# Switch_Video_con_PIC.net
KiCad netlist of a schematic drawn in Altium Designer
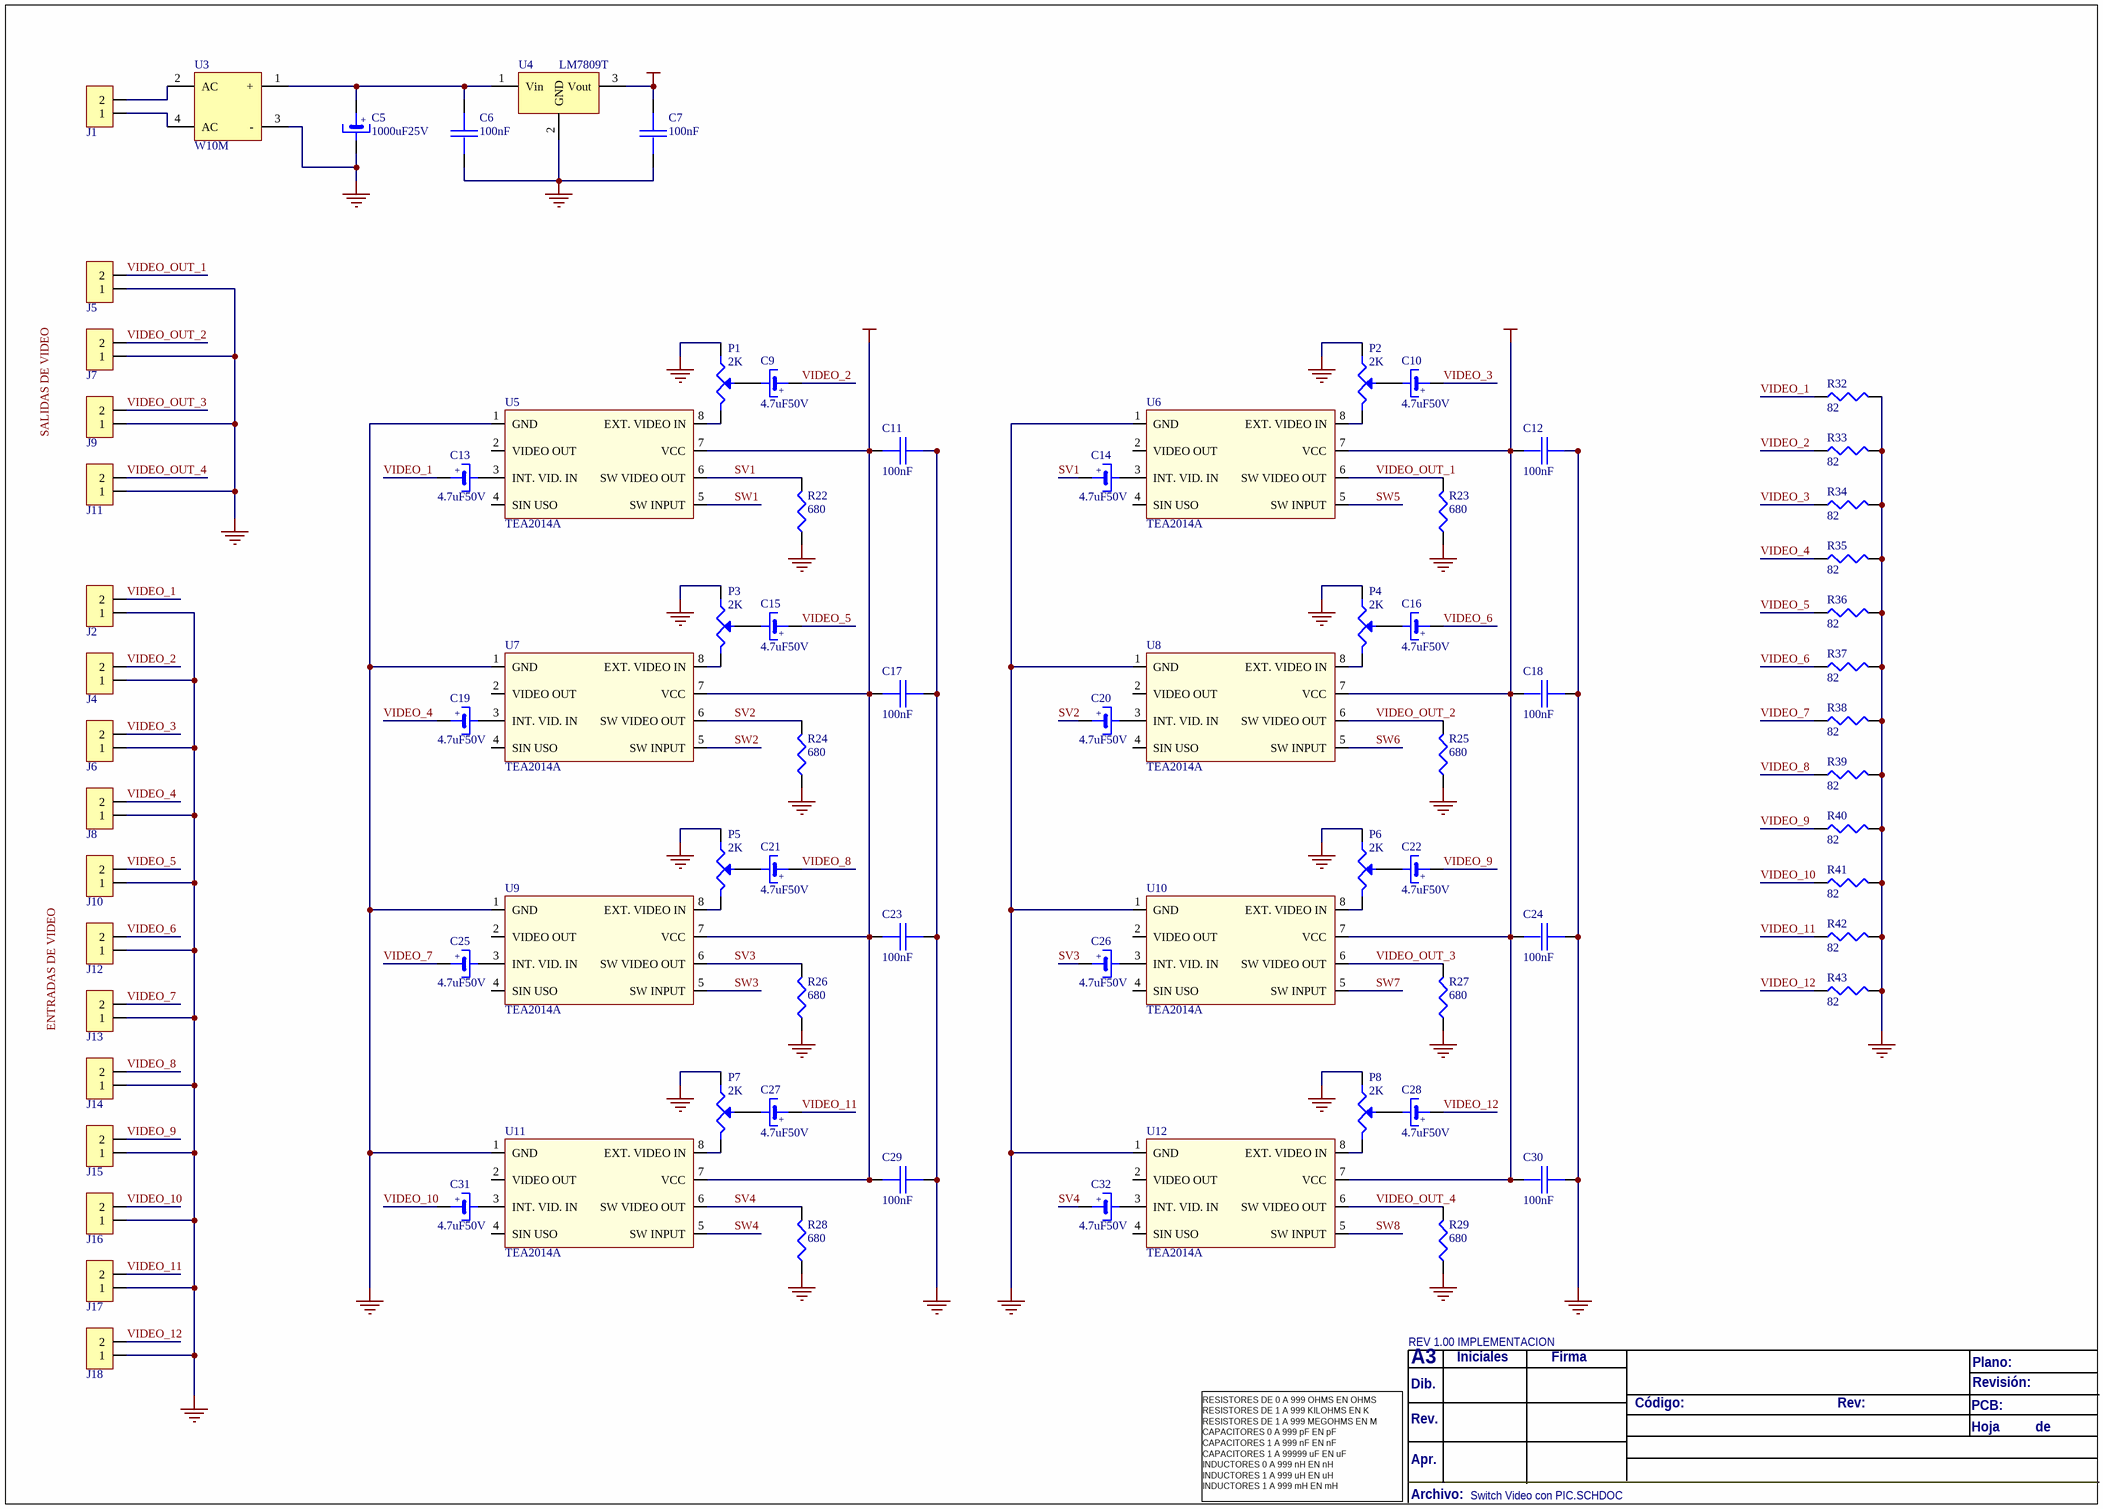
[diagram p0: Switch Video con PIC.SCHDOC]

(export (version "E")
  (design (tool "Eeschema 10.0.6"))
  (components
    (comp (ref "C5")
      (value "1000uF25V")
      (footprint "CE 5.0/12.5")
      (description "CAPACITOR ELECTROLITICO RADIAL  HFC EPCOS 12.5 X 20 mm PASO 5 mm +/-20% 105ºC 25V 1000uF")
      (libsource (lib "CAPACITORES ELECTROLITICOS") (part "1000uF25V HFC"))
    )
    (comp (ref "C6")
      (value "100nF")
      (footprint "0805")
      (description "CAPACITOR SMD 0805 X7R  50 V 100 nF")
      (libsource (lib "CAPACITORES SMD0805") (part "100n"))
    )
    (comp (ref "C7")
      (value "100nF")
      (footprint "0805")
      (description "CAPACITOR SMD 0805 X7R  50 V 100 nF")
      (libsource (lib "CAPACITORES SMD0805") (part "100n"))
    )
    (comp (ref "C9")
      (value "4.7uF50V")
      (footprint "CE 2.5/5.0")
      (description "CAPACITOR ELECTROLITICO RADIAL 5 X11mm PASO 2 mm 85ºC +/-20% 50 V 4.7 uF")
      (libsource (lib "CAPACITORES ELECTROLITICOS") (part "4.7uF50V"))
    )
    (comp (ref "C10")
      (value "4.7uF50V")
      (footprint "CE 2.5/5.0")
      (description "CAPACITOR ELECTROLITICO RADIAL 5 X11mm PASO 2 mm 85ºC +/-20% 50 V 4.7 uF")
      (libsource (lib "CAPACITORES ELECTROLITICOS") (part "4.7uF50V"))
    )
    (comp (ref "C11")
      (value "100nF")
      (footprint "CAP5.08")
      (description "CAPACITOR CERAMICO DISCO 2.54 mm  X7R  50V  100nF")
      (libsource (lib "CAPACITORES CERAMICO DISCO") (part "100n"))
    )
    (comp (ref "C12")
      (value "100nF")
      (footprint "CAP5.08")
      (description "CAPACITOR CERAMICO DISCO 2.54 mm  X7R  50V  100nF")
      (libsource (lib "CAPACITORES CERAMICO DISCO") (part "100n"))
    )
    (comp (ref "C13")
      (value "4.7uF50V")
      (footprint "CE 2.5/5.0")
      (description "CAPACITOR ELECTROLITICO RADIAL 5 X11mm PASO 2 mm 85ºC +/-20% 50 V 4.7 uF")
      (libsource (lib "CAPACITORES ELECTROLITICOS") (part "4.7uF50V"))
    )
    (comp (ref "C14")
      (value "4.7uF50V")
      (footprint "CE 2.5/5.0")
      (description "CAPACITOR ELECTROLITICO RADIAL 5 X11mm PASO 2 mm 85ºC +/-20% 50 V 4.7 uF")
      (libsource (lib "CAPACITORES ELECTROLITICOS") (part "4.7uF50V"))
    )
    (comp (ref "C15")
      (value "4.7uF50V")
      (footprint "CE 2.5/5.0")
      (description "CAPACITOR ELECTROLITICO RADIAL 5 X11mm PASO 2 mm 85ºC +/-20% 50 V 4.7 uF")
      (libsource (lib "CAPACITORES ELECTROLITICOS") (part "4.7uF50V"))
    )
    (comp (ref "C16")
      (value "4.7uF50V")
      (footprint "CE 2.5/5.0")
      (description "CAPACITOR ELECTROLITICO RADIAL 5 X11mm PASO 2 mm 85ºC +/-20% 50 V 4.7 uF")
      (libsource (lib "CAPACITORES ELECTROLITICOS") (part "4.7uF50V"))
    )
    (comp (ref "C17")
      (value "100nF")
      (footprint "CAP5.08")
      (description "CAPACITOR CERAMICO DISCO 2.54 mm  X7R  50V  100nF")
      (libsource (lib "CAPACITORES CERAMICO DISCO") (part "100n"))
    )
    (comp (ref "C18")
      (value "100nF")
      (footprint "CAP5.08")
      (description "CAPACITOR CERAMICO DISCO 2.54 mm  X7R  50V  100nF")
      (libsource (lib "CAPACITORES CERAMICO DISCO") (part "100n"))
    )
    (comp (ref "C19")
      (value "4.7uF50V")
      (footprint "CE 2.5/5.0")
      (description "CAPACITOR ELECTROLITICO RADIAL 5 X11mm PASO 2 mm 85ºC +/-20% 50 V 4.7 uF")
      (libsource (lib "CAPACITORES ELECTROLITICOS") (part "4.7uF50V"))
    )
    (comp (ref "C20")
      (value "4.7uF50V")
      (footprint "CE 2.5/5.0")
      (description "CAPACITOR ELECTROLITICO RADIAL 5 X11mm PASO 2 mm 85ºC +/-20% 50 V 4.7 uF")
      (libsource (lib "CAPACITORES ELECTROLITICOS") (part "4.7uF50V"))
    )
    (comp (ref "C21")
      (value "4.7uF50V")
      (footprint "CE 2.5/5.0")
      (description "CAPACITOR ELECTROLITICO RADIAL 5 X11mm PASO 2 mm 85ºC +/-20% 50 V 4.7 uF")
      (libsource (lib "CAPACITORES ELECTROLITICOS") (part "4.7uF50V"))
    )
    (comp (ref "C22")
      (value "4.7uF50V")
      (footprint "CE 2.5/5.0")
      (description "CAPACITOR ELECTROLITICO RADIAL 5 X11mm PASO 2 mm 85ºC +/-20% 50 V 4.7 uF")
      (libsource (lib "CAPACITORES ELECTROLITICOS") (part "4.7uF50V"))
    )
    (comp (ref "C23")
      (value "100nF")
      (footprint "CAP5.08")
      (description "CAPACITOR CERAMICO DISCO 2.54 mm  X7R  50V  100nF")
      (libsource (lib "CAPACITORES CERAMICO DISCO") (part "100n"))
    )
    (comp (ref "C24")
      (value "100nF")
      (footprint "CAP5.08")
      (description "CAPACITOR CERAMICO DISCO 2.54 mm  X7R  50V  100nF")
      (libsource (lib "CAPACITORES CERAMICO DISCO") (part "100n"))
    )
    (comp (ref "C25")
      (value "4.7uF50V")
      (footprint "CE 2.5/5.0")
      (description "CAPACITOR ELECTROLITICO RADIAL 5 X11mm PASO 2 mm 85ºC +/-20% 50 V 4.7 uF")
      (libsource (lib "CAPACITORES ELECTROLITICOS") (part "4.7uF50V"))
    )
    (comp (ref "C26")
      (value "4.7uF50V")
      (footprint "CE 2.5/5.0")
      (description "CAPACITOR ELECTROLITICO RADIAL 5 X11mm PASO 2 mm 85ºC +/-20% 50 V 4.7 uF")
      (libsource (lib "CAPACITORES ELECTROLITICOS") (part "4.7uF50V"))
    )
    (comp (ref "C27")
      (value "4.7uF50V")
      (footprint "CE 2.5/5.0")
      (description "CAPACITOR ELECTROLITICO RADIAL 5 X11mm PASO 2 mm 85ºC +/-20% 50 V 4.7 uF")
      (libsource (lib "CAPACITORES ELECTROLITICOS") (part "4.7uF50V"))
    )
    (comp (ref "C28")
      (value "4.7uF50V")
      (footprint "CE 2.5/5.0")
      (description "CAPACITOR ELECTROLITICO RADIAL 5 X11mm PASO 2 mm 85ºC +/-20% 50 V 4.7 uF")
      (libsource (lib "CAPACITORES ELECTROLITICOS") (part "4.7uF50V"))
    )
    (comp (ref "C29")
      (value "100nF")
      (footprint "CAP5.08")
      (description "CAPACITOR CERAMICO DISCO 2.54 mm  X7R  50V  100nF")
      (libsource (lib "CAPACITORES CERAMICO DISCO") (part "100n"))
    )
    (comp (ref "C30")
      (value "100nF")
      (footprint "CAP5.08")
      (description "CAPACITOR CERAMICO DISCO 2.54 mm  X7R  50V  100nF")
      (libsource (lib "CAPACITORES CERAMICO DISCO") (part "100n"))
    )
    (comp (ref "C31")
      (value "4.7uF50V")
      (footprint "CE 2.5/5.0")
      (description "CAPACITOR ELECTROLITICO RADIAL 5 X11mm PASO 2 mm 85ºC +/-20% 50 V 4.7 uF")
      (libsource (lib "CAPACITORES ELECTROLITICOS") (part "4.7uF50V"))
    )
    (comp (ref "C32")
      (value "4.7uF50V")
      (footprint "CE 2.5/5.0")
      (description "CAPACITOR ELECTROLITICO RADIAL 5 X11mm PASO 2 mm 85ºC +/-20% 50 V 4.7 uF")
      (libsource (lib "CAPACITORES ELECTROLITICOS") (part "4.7uF50V"))
    )
    (comp (ref "J1")
      (value "PW2S")
      (footprint "PW2S")
      (description "PW2S HEADER .156\" RECTO 2 VIAS")
      (libsource (lib "CONECTORES") (part "PW2S"))
    )
    (comp (ref "J2")
      (value "PW2S")
      (footprint "PW2S")
      (description "PW2S HEADER .156\" RECTO 2 VIAS")
      (libsource (lib "CONECTORES") (part "PW2S"))
    )
    (comp (ref "J4")
      (value "PW2S")
      (footprint "PW2S")
      (description "PW2S HEADER .156\" RECTO 2 VIAS")
      (libsource (lib "CONECTORES") (part "PW2S"))
    )
    (comp (ref "J5")
      (value "PW2S")
      (footprint "PW2S")
      (description "PW2S HEADER .156\" RECTO 2 VIAS")
      (libsource (lib "CONECTORES") (part "PW2S"))
    )
    (comp (ref "J6")
      (value "PW2S")
      (footprint "PW2S")
      (description "PW2S HEADER .156\" RECTO 2 VIAS")
      (libsource (lib "CONECTORES") (part "PW2S"))
    )
    (comp (ref "J7")
      (value "PW2S")
      (footprint "PW2S")
      (description "PW2S HEADER .156\" RECTO 2 VIAS")
      (libsource (lib "CONECTORES") (part "PW2S"))
    )
    (comp (ref "J8")
      (value "PW2S")
      (footprint "PW2S")
      (description "PW2S HEADER .156\" RECTO 2 VIAS")
      (libsource (lib "CONECTORES") (part "PW2S"))
    )
    (comp (ref "J9")
      (value "PW2S")
      (footprint "PW2S")
      (description "PW2S HEADER .156\" RECTO 2 VIAS")
      (libsource (lib "CONECTORES") (part "PW2S"))
    )
    (comp (ref "J10")
      (value "PW2S")
      (footprint "PW2S")
      (description "PW2S HEADER .156\" RECTO 2 VIAS")
      (libsource (lib "CONECTORES") (part "PW2S"))
    )
    (comp (ref "J11")
      (value "PW2S")
      (footprint "PW2S")
      (description "PW2S HEADER .156\" RECTO 2 VIAS")
      (libsource (lib "CONECTORES") (part "PW2S"))
    )
    (comp (ref "J12")
      (value "PW2S")
      (footprint "PW2S")
      (description "PW2S HEADER .156\" RECTO 2 VIAS")
      (libsource (lib "CONECTORES") (part "PW2S"))
    )
    (comp (ref "J13")
      (value "PW2S")
      (footprint "PW2S")
      (description "PW2S HEADER .156\" RECTO 2 VIAS")
      (libsource (lib "CONECTORES") (part "PW2S"))
    )
    (comp (ref "J14")
      (value "PW2S")
      (footprint "PW2S")
      (description "PW2S HEADER .156\" RECTO 2 VIAS")
      (libsource (lib "CONECTORES") (part "PW2S"))
    )
    (comp (ref "J15")
      (value "PW2S")
      (footprint "PW2S")
      (description "PW2S HEADER .156\" RECTO 2 VIAS")
      (libsource (lib "CONECTORES") (part "PW2S"))
    )
    (comp (ref "J16")
      (value "PW2S")
      (footprint "PW2S")
      (description "PW2S HEADER .156\" RECTO 2 VIAS")
      (libsource (lib "CONECTORES") (part "PW2S"))
    )
    (comp (ref "J17")
      (value "PW2S")
      (footprint "PW2S")
      (description "PW2S HEADER .156\" RECTO 2 VIAS")
      (libsource (lib "CONECTORES") (part "PW2S"))
    )
    (comp (ref "J18")
      (value "PW2S")
      (footprint "PW2S")
      (description "PW2S HEADER .156\" RECTO 2 VIAS")
      (libsource (lib "CONECTORES") (part "PW2S"))
    )
    (comp (ref "P1")
      (value "2K")
      (footprint "BOURNS3296W")
      (description "TRIMPOT BOURNS 3296W 2 KILOHMS")
      (libsource (lib "TRIMPOT") (part "BOURNS 3296W 202"))
    )
    (comp (ref "P2")
      (value "2K")
      (footprint "BOURNS3296W")
      (description "TRIMPOT BOURNS 3296W 2 KILOHMS")
      (libsource (lib "TRIMPOT") (part "BOURNS 3296W 202"))
    )
    (comp (ref "P3")
      (value "2K")
      (footprint "BOURNS3296W")
      (description "TRIMPOT BOURNS 3296W 2 KILOHMS")
      (libsource (lib "TRIMPOT") (part "BOURNS 3296W 202"))
    )
    (comp (ref "P4")
      (value "2K")
      (footprint "BOURNS3296W")
      (description "TRIMPOT BOURNS 3296W 2 KILOHMS")
      (libsource (lib "TRIMPOT") (part "BOURNS 3296W 202"))
    )
    (comp (ref "P5")
      (value "2K")
      (footprint "BOURNS3296W")
      (description "TRIMPOT BOURNS 3296W 2 KILOHMS")
      (libsource (lib "TRIMPOT") (part "BOURNS 3296W 202"))
    )
    (comp (ref "P6")
      (value "2K")
      (footprint "BOURNS3296W")
      (description "TRIMPOT BOURNS 3296W 2 KILOHMS")
      (libsource (lib "TRIMPOT") (part "BOURNS 3296W 202"))
    )
    (comp (ref "P7")
      (value "2K")
      (footprint "BOURNS3296W")
      (description "TRIMPOT BOURNS 3296W 2 KILOHMS")
      (libsource (lib "TRIMPOT") (part "BOURNS 3296W 202"))
    )
    (comp (ref "P8")
      (value "2K")
      (footprint "BOURNS3296W")
      (description "TRIMPOT BOURNS 3296W 2 KILOHMS")
      (libsource (lib "TRIMPOT") (part "BOURNS 3296W 202"))
    )
    (comp (ref "R22")
      (value "680")
      (footprint "RES_MF1/2W_200")
      (description "RESISTOR METAL FILM 0.5 W 5% 680 OHMS")
      (libsource (lib "RESISTORES METAL FILM MEDIO WATT") (part "680"))
    )
    (comp (ref "R23")
      (value "680")
      (footprint "RES_MF1/2W_200")
      (description "RESISTOR METAL FILM 0.5 W 5% 680 OHMS")
      (libsource (lib "RESISTORES METAL FILM MEDIO WATT") (part "680"))
    )
    (comp (ref "R24")
      (value "680")
      (footprint "RES_MF1/2W_200")
      (description "RESISTOR METAL FILM 0.5 W 5% 680 OHMS")
      (libsource (lib "RESISTORES METAL FILM MEDIO WATT") (part "680"))
    )
    (comp (ref "R25")
      (value "680")
      (footprint "RES_MF1/2W_200")
      (description "RESISTOR METAL FILM 0.5 W 5% 680 OHMS")
      (libsource (lib "RESISTORES METAL FILM MEDIO WATT") (part "680"))
    )
    (comp (ref "R26")
      (value "680")
      (footprint "RES_MF1/2W_200")
      (description "RESISTOR METAL FILM 0.5 W 5% 680 OHMS")
      (libsource (lib "RESISTORES METAL FILM MEDIO WATT") (part "680"))
    )
    (comp (ref "R27")
      (value "680")
      (footprint "RES_MF1/2W_200")
      (description "RESISTOR METAL FILM 0.5 W 5% 680 OHMS")
      (libsource (lib "RESISTORES METAL FILM MEDIO WATT") (part "680"))
    )
    (comp (ref "R28")
      (value "680")
      (footprint "RES_MF1/2W_200")
      (description "RESISTOR METAL FILM 0.5 W 5% 680 OHMS")
      (libsource (lib "RESISTORES METAL FILM MEDIO WATT") (part "680"))
    )
    (comp (ref "R29")
      (value "680")
      (footprint "RES_MF1/2W_200")
      (description "RESISTOR METAL FILM 0.5 W 5% 680 OHMS")
      (libsource (lib "RESISTORES METAL FILM MEDIO WATT") (part "680"))
    )
    (comp (ref "R32")
      (value "82")
      (footprint "0805")
      (description "RESISTOR SMD0805 0.125 W 5%  82 OHMS")
      (libsource (lib "RESISTORES SMD0805") (part "82"))
    )
    (comp (ref "R33")
      (value "82")
      (footprint "0805")
      (description "RESISTOR SMD0805 0.125 W 5%  82 OHMS")
      (libsource (lib "RESISTORES SMD0805") (part "82"))
    )
    (comp (ref "R34")
      (value "82")
      (footprint "0805")
      (description "RESISTOR SMD0805 0.125 W 5%  82 OHMS")
      (libsource (lib "RESISTORES SMD0805") (part "82"))
    )
    (comp (ref "R35")
      (value "82")
      (footprint "0805")
      (description "RESISTOR SMD0805 0.125 W 5%  82 OHMS")
      (libsource (lib "RESISTORES SMD0805") (part "82"))
    )
    (comp (ref "R36")
      (value "82")
      (footprint "0805")
      (description "RESISTOR SMD0805 0.125 W 5%  82 OHMS")
      (libsource (lib "RESISTORES SMD0805") (part "82"))
    )
    (comp (ref "R37")
      (value "82")
      (footprint "0805")
      (description "RESISTOR SMD0805 0.125 W 5%  82 OHMS")
      (libsource (lib "RESISTORES SMD0805") (part "82"))
    )
    (comp (ref "R38")
      (value "82")
      (footprint "0805")
      (description "RESISTOR SMD0805 0.125 W 5%  82 OHMS")
      (libsource (lib "RESISTORES SMD0805") (part "82"))
    )
    (comp (ref "R39")
      (value "82")
      (footprint "0805")
      (description "RESISTOR SMD0805 0.125 W 5%  82 OHMS")
      (libsource (lib "RESISTORES SMD0805") (part "82"))
    )
    (comp (ref "R40")
      (value "82")
      (footprint "0805")
      (description "RESISTOR SMD0805 0.125 W 5%  82 OHMS")
      (libsource (lib "RESISTORES SMD0805") (part "82"))
    )
    (comp (ref "R41")
      (value "82")
      (footprint "0805")
      (description "RESISTOR SMD0805 0.125 W 5%  82 OHMS")
      (libsource (lib "RESISTORES SMD0805") (part "82"))
    )
    (comp (ref "R42")
      (value "82")
      (footprint "0805")
      (description "RESISTOR SMD0805 0.125 W 5%  82 OHMS")
      (libsource (lib "RESISTORES SMD0805") (part "82"))
    )
    (comp (ref "R43")
      (value "82")
      (footprint "0805")
      (description "RESISTOR SMD0805 0.125 W 5%  82 OHMS")
      (libsource (lib "RESISTORES SMD0805") (part "82"))
    )
    (comp (ref "U3")
      (value "W10M")
      (footprint "CASE22")
      (description "W10M CASE22 CIRC INT RECTIFICADOR PUENTE 1000V 1A")
      (libsource (lib "CIRCUITOS INTEGRADOS DIP") (part "W10M"))
    )
    (comp (ref "U4")
      (value "LM7809T")
      (footprint "TO-220_1")
      (description "LM7809T TO-220 CIRC INT")
      (libsource (lib "CIRCUITOS INTEGRADOS DIP") (part "LM7809T"))
    )
    (comp (ref "U5")
      (value "TEA2014A")
      (footprint "DIP8")
      (description "TEA2014A DIP-8 VIDEO SWITCH")
      (libsource (lib "CIRCUITOS INTEGRADOS DIP") (part "TEA2014A"))
    )
    (comp (ref "U6")
      (value "TEA2014A")
      (footprint "DIP8")
      (description "TEA2014A DIP-8 VIDEO SWITCH")
      (libsource (lib "CIRCUITOS INTEGRADOS DIP") (part "TEA2014A"))
    )
    (comp (ref "U7")
      (value "TEA2014A")
      (footprint "DIP8")
      (description "TEA2014A DIP-8 VIDEO SWITCH")
      (libsource (lib "CIRCUITOS INTEGRADOS DIP") (part "TEA2014A"))
    )
    (comp (ref "U8")
      (value "TEA2014A")
      (footprint "DIP8")
      (description "TEA2014A DIP-8 VIDEO SWITCH")
      (libsource (lib "CIRCUITOS INTEGRADOS DIP") (part "TEA2014A"))
    )
    (comp (ref "U9")
      (value "TEA2014A")
      (footprint "DIP8")
      (description "TEA2014A DIP-8 VIDEO SWITCH")
      (libsource (lib "CIRCUITOS INTEGRADOS DIP") (part "TEA2014A"))
    )
    (comp (ref "U10")
      (value "TEA2014A")
      (footprint "DIP8")
      (description "TEA2014A DIP-8 VIDEO SWITCH")
      (libsource (lib "CIRCUITOS INTEGRADOS DIP") (part "TEA2014A"))
    )
    (comp (ref "U11")
      (value "TEA2014A")
      (footprint "DIP8")
      (description "TEA2014A DIP-8 VIDEO SWITCH")
      (libsource (lib "CIRCUITOS INTEGRADOS DIP") (part "TEA2014A"))
    )
    (comp (ref "U12")
      (value "TEA2014A")
      (footprint "DIP8")
      (description "TEA2014A DIP-8 VIDEO SWITCH")
      (libsource (lib "CIRCUITOS INTEGRADOS DIP") (part "TEA2014A"))
    )
  )
  (nets
    (net (code "3") (name "/SV1") (class "Default")
      (node (ref "C14") (pin "1") (pinfunction "1_1") (pintype "passive"))
      (node (ref "R22") (pin "2") (pintype "passive"))
      (node (ref "U5") (pin "6") (pinfunction "SW_VIDEO_OUT_6") (pintype "passive"))
    )
    (net (code "4") (name "/SV2") (class "Default")
      (node (ref "C20") (pin "1") (pinfunction "1_1") (pintype "passive"))
      (node (ref "R24") (pin "2") (pintype "passive"))
      (node (ref "U7") (pin "6") (pinfunction "SW_VIDEO_OUT_6") (pintype "passive"))
    )
    (net (code "5") (name "/SV3") (class "Default")
      (node (ref "C26") (pin "1") (pinfunction "1_1") (pintype "passive"))
      (node (ref "R26") (pin "2") (pintype "passive"))
      (node (ref "U9") (pin "6") (pinfunction "SW_VIDEO_OUT_6") (pintype "passive"))
    )
    (net (code "6") (name "/SV4") (class "Default")
      (node (ref "C32") (pin "1") (pinfunction "1_1") (pintype "passive"))
      (node (ref "R28") (pin "2") (pintype "passive"))
      (node (ref "U11") (pin "6") (pinfunction "SW_VIDEO_OUT_6") (pintype "passive"))
    )
    (net (code "7") (name "/SW1") (class "Default")
      (node (ref "U5") (pin "5") (pinfunction "SW_INPUT_5") (pintype "power_in"))
    )
    (net (code "8") (name "/SW2") (class "Default")
      (node (ref "U7") (pin "5") (pinfunction "SW_INPUT_5") (pintype "power_in"))
    )
    (net (code "9") (name "/SW3") (class "Default")
      (node (ref "U9") (pin "5") (pinfunction "SW_INPUT_5") (pintype "power_in"))
    )
    (net (code "10") (name "/SW4") (class "Default")
      (node (ref "U11") (pin "5") (pinfunction "SW_INPUT_5") (pintype "power_in"))
    )
    (net (code "11") (name "/SW5") (class "Default")
      (node (ref "U6") (pin "5") (pinfunction "SW_INPUT_5") (pintype "power_in"))
    )
    (net (code "12") (name "/SW6") (class "Default")
      (node (ref "U8") (pin "5") (pinfunction "SW_INPUT_5") (pintype "power_in"))
    )
    (net (code "13") (name "/SW7") (class "Default")
      (node (ref "U10") (pin "5") (pinfunction "SW_INPUT_5") (pintype "power_in"))
    )
    (net (code "14") (name "/SW8") (class "Default")
      (node (ref "U12") (pin "5") (pinfunction "SW_INPUT_5") (pintype "power_in"))
    )
    (net (code "15") (name "/VIDEO_1") (class "Default")
      (node (ref "C13") (pin "1") (pinfunction "1_1") (pintype "passive"))
      (node (ref "J2") (pin "2") (pinfunction "2_2") (pintype "passive"))
      (node (ref "R32") (pin "1") (pintype "passive"))
    )
    (net (code "16") (name "/VIDEO_2") (class "Default")
      (node (ref "C9") (pin "1") (pinfunction "1_1") (pintype "passive"))
      (node (ref "J4") (pin "2") (pinfunction "2_2") (pintype "passive"))
      (node (ref "R33") (pin "1") (pintype "passive"))
    )
    (net (code "17") (name "/VIDEO_3") (class "Default")
      (node (ref "C10") (pin "1") (pinfunction "1_1") (pintype "passive"))
      (node (ref "J6") (pin "2") (pinfunction "2_2") (pintype "passive"))
      (node (ref "R34") (pin "1") (pintype "passive"))
    )
    (net (code "18") (name "/VIDEO_4") (class "Default")
      (node (ref "C19") (pin "1") (pinfunction "1_1") (pintype "passive"))
      (node (ref "J8") (pin "2") (pinfunction "2_2") (pintype "passive"))
      (node (ref "R35") (pin "1") (pintype "passive"))
    )
    (net (code "19") (name "/VIDEO_5") (class "Default")
      (node (ref "C15") (pin "1") (pinfunction "1_1") (pintype "passive"))
      (node (ref "J10") (pin "2") (pinfunction "2_2") (pintype "passive"))
      (node (ref "R36") (pin "1") (pintype "passive"))
    )
    (net (code "20") (name "/VIDEO_6") (class "Default")
      (node (ref "C16") (pin "1") (pinfunction "1_1") (pintype "passive"))
      (node (ref "J12") (pin "2") (pinfunction "2_2") (pintype "passive"))
      (node (ref "R37") (pin "1") (pintype "passive"))
    )
    (net (code "21") (name "/VIDEO_7") (class "Default")
      (node (ref "C25") (pin "1") (pinfunction "1_1") (pintype "passive"))
      (node (ref "J13") (pin "2") (pinfunction "2_2") (pintype "passive"))
      (node (ref "R38") (pin "1") (pintype "passive"))
    )
    (net (code "22") (name "/VIDEO_8") (class "Default")
      (node (ref "C21") (pin "1") (pinfunction "1_1") (pintype "passive"))
      (node (ref "J14") (pin "2") (pinfunction "2_2") (pintype "passive"))
      (node (ref "R39") (pin "1") (pintype "passive"))
    )
    (net (code "23") (name "/VIDEO_9") (class "Default")
      (node (ref "C22") (pin "1") (pinfunction "1_1") (pintype "passive"))
      (node (ref "J15") (pin "2") (pinfunction "2_2") (pintype "passive"))
      (node (ref "R40") (pin "1") (pintype "passive"))
    )
    (net (code "24") (name "/VIDEO_10") (class "Default")
      (node (ref "C31") (pin "1") (pinfunction "1_1") (pintype "passive"))
      (node (ref "J16") (pin "2") (pinfunction "2_2") (pintype "passive"))
      (node (ref "R41") (pin "1") (pintype "passive"))
    )
    (net (code "25") (name "/VIDEO_11") (class "Default")
      (node (ref "C27") (pin "1") (pinfunction "1_1") (pintype "passive"))
      (node (ref "J17") (pin "2") (pinfunction "2_2") (pintype "passive"))
      (node (ref "R42") (pin "1") (pintype "passive"))
    )
    (net (code "26") (name "/VIDEO_12") (class "Default")
      (node (ref "C28") (pin "1") (pinfunction "1_1") (pintype "passive"))
      (node (ref "J18") (pin "2") (pinfunction "2_2") (pintype "passive"))
      (node (ref "R43") (pin "1") (pintype "passive"))
    )
    (net (code "27") (name "/VIDEO_OUT_1") (class "Default")
      (node (ref "J5") (pin "2") (pinfunction "2_2") (pintype "passive"))
      (node (ref "R23") (pin "2") (pintype "passive"))
      (node (ref "U6") (pin "6") (pinfunction "SW_VIDEO_OUT_6") (pintype "passive"))
    )
    (net (code "28") (name "/VIDEO_OUT_2") (class "Default")
      (node (ref "J7") (pin "2") (pinfunction "2_2") (pintype "passive"))
      (node (ref "R25") (pin "2") (pintype "passive"))
      (node (ref "U8") (pin "6") (pinfunction "SW_VIDEO_OUT_6") (pintype "passive"))
    )
    (net (code "29") (name "/VIDEO_OUT_3") (class "Default")
      (node (ref "J9") (pin "2") (pinfunction "2_2") (pintype "passive"))
      (node (ref "R27") (pin "2") (pintype "passive"))
      (node (ref "U10") (pin "6") (pinfunction "SW_VIDEO_OUT_6") (pintype "passive"))
    )
    (net (code "30") (name "/VIDEO_OUT_4") (class "Default")
      (node (ref "J11") (pin "2") (pinfunction "2_2") (pintype "passive"))
      (node (ref "R29") (pin "2") (pintype "passive"))
      (node (ref "U12") (pin "6") (pinfunction "SW_VIDEO_OUT_6") (pintype "passive"))
    )
    (net (code "31") (name "GND") (class "Default")
      (node (ref "C11") (pin "2") (pintype "passive"))
      (node (ref "C12") (pin "2") (pintype "passive"))
      (node (ref "C17") (pin "2") (pintype "passive"))
      (node (ref "C18") (pin "2") (pintype "passive"))
      (node (ref "C23") (pin "2") (pintype "passive"))
      (node (ref "C24") (pin "2") (pintype "passive"))
      (node (ref "C29") (pin "2") (pintype "passive"))
      (node (ref "C30") (pin "2") (pintype "passive"))
      (node (ref "C5") (pin "2") (pinfunction "2_2") (pintype "passive"))
      (node (ref "C6") (pin "1") (pintype "passive"))
      (node (ref "C7") (pin "1") (pintype "passive"))
      (node (ref "J10") (pin "1") (pinfunction "1_1") (pintype "passive"))
      (node (ref "J11") (pin "1") (pinfunction "1_1") (pintype "passive"))
      (node (ref "J12") (pin "1") (pinfunction "1_1") (pintype "passive"))
      (node (ref "J13") (pin "1") (pinfunction "1_1") (pintype "passive"))
      (node (ref "J14") (pin "1") (pinfunction "1_1") (pintype "passive"))
      (node (ref "J15") (pin "1") (pinfunction "1_1") (pintype "passive"))
      (node (ref "J16") (pin "1") (pinfunction "1_1") (pintype "passive"))
      (node (ref "J17") (pin "1") (pinfunction "1_1") (pintype "passive"))
      (node (ref "J18") (pin "1") (pinfunction "1_1") (pintype "passive"))
      (node (ref "J2") (pin "1") (pinfunction "1_1") (pintype "passive"))
      (node (ref "J4") (pin "1") (pinfunction "1_1") (pintype "passive"))
      (node (ref "J5") (pin "1") (pinfunction "1_1") (pintype "passive"))
      (node (ref "J6") (pin "1") (pinfunction "1_1") (pintype "passive"))
      (node (ref "J7") (pin "1") (pinfunction "1_1") (pintype "passive"))
      (node (ref "J8") (pin "1") (pinfunction "1_1") (pintype "passive"))
      (node (ref "J9") (pin "1") (pinfunction "1_1") (pintype "passive"))
      (node (ref "P1") (pin "1") (pintype "passive"))
      (node (ref "P2") (pin "1") (pintype "passive"))
      (node (ref "P3") (pin "1") (pintype "passive"))
      (node (ref "P4") (pin "1") (pintype "passive"))
      (node (ref "P5") (pin "1") (pintype "passive"))
      (node (ref "P6") (pin "1") (pintype "passive"))
      (node (ref "P7") (pin "1") (pintype "passive"))
      (node (ref "P8") (pin "1") (pintype "passive"))
      (node (ref "R22") (pin "1") (pintype "passive"))
      (node (ref "R23") (pin "1") (pintype "passive"))
      (node (ref "R24") (pin "1") (pintype "passive"))
      (node (ref "R25") (pin "1") (pintype "passive"))
      (node (ref "R26") (pin "1") (pintype "passive"))
      (node (ref "R27") (pin "1") (pintype "passive"))
      (node (ref "R28") (pin "1") (pintype "passive"))
      (node (ref "R29") (pin "1") (pintype "passive"))
      (node (ref "R32") (pin "2") (pintype "passive"))
      (node (ref "R33") (pin "2") (pintype "passive"))
      (node (ref "R34") (pin "2") (pintype "passive"))
      (node (ref "R35") (pin "2") (pintype "passive"))
      (node (ref "R36") (pin "2") (pintype "passive"))
      (node (ref "R37") (pin "2") (pintype "passive"))
      (node (ref "R38") (pin "2") (pintype "passive"))
      (node (ref "R39") (pin "2") (pintype "passive"))
      (node (ref "R40") (pin "2") (pintype "passive"))
      (node (ref "R41") (pin "2") (pintype "passive"))
      (node (ref "R42") (pin "2") (pintype "passive"))
      (node (ref "R43") (pin "2") (pintype "passive"))
      (node (ref "U10") (pin "1") (pinfunction "GND_1") (pintype "passive"))
      (node (ref "U11") (pin "1") (pinfunction "GND_1") (pintype "passive"))
      (node (ref "U12") (pin "1") (pinfunction "GND_1") (pintype "passive"))
      (node (ref "U3") (pin "3") (pinfunction "-_3") (pintype "passive"))
      (node (ref "U4") (pin "2") (pinfunction "GND_2") (pintype "passive"))
      (node (ref "U5") (pin "1") (pinfunction "GND_1") (pintype "passive"))
      (node (ref "U6") (pin "1") (pinfunction "GND_1") (pintype "passive"))
      (node (ref "U7") (pin "1") (pinfunction "GND_1") (pintype "passive"))
      (node (ref "U8") (pin "1") (pinfunction "GND_1") (pintype "passive"))
      (node (ref "U9") (pin "1") (pinfunction "GND_1") (pintype "passive"))
    )
    (net (code "32") (name "Net-(C9-Pad2)") (class "Default")
      (node (ref "C9") (pin "2") (pinfunction "2_2") (pintype "passive"))
      (node (ref "P1") (pin "2") (pintype "passive"))
    )
    (net (code "33") (name "Net-(C10-Pad2)") (class "Default")
      (node (ref "C10") (pin "2") (pinfunction "2_2") (pintype "passive"))
      (node (ref "P2") (pin "2") (pintype "passive"))
    )
    (net (code "34") (name "Net-(C15-Pad2)") (class "Default")
      (node (ref "C15") (pin "2") (pinfunction "2_2") (pintype "passive"))
      (node (ref "P3") (pin "2") (pintype "passive"))
    )
    (net (code "35") (name "Net-(C16-Pad2)") (class "Default")
      (node (ref "C16") (pin "2") (pinfunction "2_2") (pintype "passive"))
      (node (ref "P4") (pin "2") (pintype "passive"))
    )
    (net (code "36") (name "Net-(C21-Pad2)") (class "Default")
      (node (ref "C21") (pin "2") (pinfunction "2_2") (pintype "passive"))
      (node (ref "P5") (pin "2") (pintype "passive"))
    )
    (net (code "37") (name "Net-(C22-Pad2)") (class "Default")
      (node (ref "C22") (pin "2") (pinfunction "2_2") (pintype "passive"))
      (node (ref "P6") (pin "2") (pintype "passive"))
    )
    (net (code "38") (name "Net-(C27-Pad2)") (class "Default")
      (node (ref "C27") (pin "2") (pinfunction "2_2") (pintype "passive"))
      (node (ref "P7") (pin "2") (pintype "passive"))
    )
    (net (code "39") (name "Net-(C28-Pad2)") (class "Default")
      (node (ref "C28") (pin "2") (pinfunction "2_2") (pintype "passive"))
      (node (ref "P8") (pin "2") (pintype "passive"))
    )
    (net (code "40") (name "Net-(J1-Pad1)") (class "Default")
      (node (ref "J1") (pin "1") (pinfunction "1_1") (pintype "passive"))
      (node (ref "U3") (pin "4") (pinfunction "AC_4") (pintype "passive"))
    )
    (net (code "41") (name "Net-(J1-Pad2)") (class "Default")
      (node (ref "J1") (pin "2") (pinfunction "2_2") (pintype "passive"))
      (node (ref "U3") (pin "2") (pinfunction "AC_2") (pintype "passive"))
    )
    (net (code "42") (name "Net-(U3-+)") (class "Default")
      (node (ref "C5") (pin "1") (pinfunction "1_1") (pintype "passive"))
      (node (ref "C6") (pin "2") (pintype "passive"))
      (node (ref "U3") (pin "1") (pinfunction "+_1") (pintype "passive"))
      (node (ref "U4") (pin "1") (pinfunction "Vin_1") (pintype "passive"))
    )
    (net (code "43") (name "Net-(U5-EXT._VIDEO_IN)") (class "Default")
      (node (ref "P1") (pin "3") (pintype "passive"))
      (node (ref "U5") (pin "8") (pinfunction "EXT._VIDEO_IN_8") (pintype "passive"))
    )
    (net (code "44") (name "Net-(U5-INT._VID._IN)") (class "Default")
      (node (ref "C13") (pin "2") (pinfunction "2_2") (pintype "passive"))
      (node (ref "U5") (pin "3") (pinfunction "INT._VID._IN_3") (pintype "passive"))
    )
    (net (code "45") (name "Net-(U6-EXT._VIDEO_IN)") (class "Default")
      (node (ref "P2") (pin "3") (pintype "passive"))
      (node (ref "U6") (pin "8") (pinfunction "EXT._VIDEO_IN_8") (pintype "passive"))
    )
    (net (code "46") (name "Net-(U6-INT._VID._IN)") (class "Default")
      (node (ref "C14") (pin "2") (pinfunction "2_2") (pintype "passive"))
      (node (ref "U6") (pin "3") (pinfunction "INT._VID._IN_3") (pintype "passive"))
    )
    (net (code "47") (name "Net-(U7-EXT._VIDEO_IN)") (class "Default")
      (node (ref "P3") (pin "3") (pintype "passive"))
      (node (ref "U7") (pin "8") (pinfunction "EXT._VIDEO_IN_8") (pintype "passive"))
    )
    (net (code "48") (name "Net-(U7-INT._VID._IN)") (class "Default")
      (node (ref "C19") (pin "2") (pinfunction "2_2") (pintype "passive"))
      (node (ref "U7") (pin "3") (pinfunction "INT._VID._IN_3") (pintype "passive"))
    )
    (net (code "49") (name "Net-(U8-EXT._VIDEO_IN)") (class "Default")
      (node (ref "P4") (pin "3") (pintype "passive"))
      (node (ref "U8") (pin "8") (pinfunction "EXT._VIDEO_IN_8") (pintype "passive"))
    )
    (net (code "50") (name "Net-(U8-INT._VID._IN)") (class "Default")
      (node (ref "C20") (pin "2") (pinfunction "2_2") (pintype "passive"))
      (node (ref "U8") (pin "3") (pinfunction "INT._VID._IN_3") (pintype "passive"))
    )
    (net (code "51") (name "Net-(U9-EXT._VIDEO_IN)") (class "Default")
      (node (ref "P5") (pin "3") (pintype "passive"))
      (node (ref "U9") (pin "8") (pinfunction "EXT._VIDEO_IN_8") (pintype "passive"))
    )
    (net (code "52") (name "Net-(U9-INT._VID._IN)") (class "Default")
      (node (ref "C25") (pin "2") (pinfunction "2_2") (pintype "passive"))
      (node (ref "U9") (pin "3") (pinfunction "INT._VID._IN_3") (pintype "passive"))
    )
    (net (code "53") (name "Net-(U10-EXT._VIDEO_IN)") (class "Default")
      (node (ref "P6") (pin "3") (pintype "passive"))
      (node (ref "U10") (pin "8") (pinfunction "EXT._VIDEO_IN_8") (pintype "passive"))
    )
    (net (code "54") (name "Net-(U10-INT._VID._IN)") (class "Default")
      (node (ref "C26") (pin "2") (pinfunction "2_2") (pintype "passive"))
      (node (ref "U10") (pin "3") (pinfunction "INT._VID._IN_3") (pintype "passive"))
    )
    (net (code "55") (name "Net-(U11-EXT._VIDEO_IN)") (class "Default")
      (node (ref "P7") (pin "3") (pintype "passive"))
      (node (ref "U11") (pin "8") (pinfunction "EXT._VIDEO_IN_8") (pintype "passive"))
    )
    (net (code "56") (name "Net-(U11-INT._VID._IN)") (class "Default")
      (node (ref "C31") (pin "2") (pinfunction "2_2") (pintype "passive"))
      (node (ref "U11") (pin "3") (pinfunction "INT._VID._IN_3") (pintype "passive"))
    )
    (net (code "57") (name "Net-(U12-EXT._VIDEO_IN)") (class "Default")
      (node (ref "P8") (pin "3") (pintype "passive"))
      (node (ref "U12") (pin "8") (pinfunction "EXT._VIDEO_IN_8") (pintype "passive"))
    )
    (net (code "58") (name "Net-(U12-INT._VID._IN)") (class "Default")
      (node (ref "C32") (pin "2") (pinfunction "2_2") (pintype "passive"))
      (node (ref "U12") (pin "3") (pinfunction "INT._VID._IN_3") (pintype "passive"))
    )
    (net (code "59") (name "VCC") (class "Default")
      (node (ref "C11") (pin "1") (pintype "passive"))
      (node (ref "C12") (pin "1") (pintype "passive"))
      (node (ref "C17") (pin "1") (pintype "passive"))
      (node (ref "C18") (pin "1") (pintype "passive"))
      (node (ref "C23") (pin "1") (pintype "passive"))
      (node (ref "C24") (pin "1") (pintype "passive"))
      (node (ref "C29") (pin "1") (pintype "passive"))
      (node (ref "C30") (pin "1") (pintype "passive"))
      (node (ref "C7") (pin "2") (pintype "passive"))
      (node (ref "U10") (pin "7") (pinfunction "VCC_7") (pintype "power_in"))
      (node (ref "U11") (pin "7") (pinfunction "VCC_7") (pintype "power_in"))
      (node (ref "U12") (pin "7") (pinfunction "VCC_7") (pintype "power_in"))
      (node (ref "U4") (pin "3") (pinfunction "Vout_3") (pintype "passive"))
      (node (ref "U5") (pin "7") (pinfunction "VCC_7") (pintype "power_in"))
      (node (ref "U6") (pin "7") (pinfunction "VCC_7") (pintype "power_in"))
      (node (ref "U7") (pin "7") (pinfunction "VCC_7") (pintype "power_in"))
      (node (ref "U8") (pin "7") (pinfunction "VCC_7") (pintype "power_in"))
      (node (ref "U9") (pin "7") (pinfunction "VCC_7") (pintype "power_in"))
    )
    (net (code "60") (name "unconnected-(U5-SIN_USO-Pad4)") (class "Default")
      (node (ref "U5") (pin "4") (pinfunction "SIN_USO_4") (pintype "passive"))
    )
    (net (code "61") (name "unconnected-(U5-VIDEO_OUT-Pad2)") (class "Default")
      (node (ref "U5") (pin "2") (pinfunction "VIDEO_OUT_2") (pintype "passive"))
    )
    (net (code "62") (name "unconnected-(U6-SIN_USO-Pad4)") (class "Default")
      (node (ref "U6") (pin "4") (pinfunction "SIN_USO_4") (pintype "passive"))
    )
    (net (code "63") (name "unconnected-(U6-VIDEO_OUT-Pad2)") (class "Default")
      (node (ref "U6") (pin "2") (pinfunction "VIDEO_OUT_2") (pintype "passive"))
    )
    (net (code "64") (name "unconnected-(U7-SIN_USO-Pad4)") (class "Default")
      (node (ref "U7") (pin "4") (pinfunction "SIN_USO_4") (pintype "passive"))
    )
    (net (code "65") (name "unconnected-(U7-VIDEO_OUT-Pad2)") (class "Default")
      (node (ref "U7") (pin "2") (pinfunction "VIDEO_OUT_2") (pintype "passive"))
    )
    (net (code "66") (name "unconnected-(U8-SIN_USO-Pad4)") (class "Default")
      (node (ref "U8") (pin "4") (pinfunction "SIN_USO_4") (pintype "passive"))
    )
    (net (code "67") (name "unconnected-(U8-VIDEO_OUT-Pad2)") (class "Default")
      (node (ref "U8") (pin "2") (pinfunction "VIDEO_OUT_2") (pintype "passive"))
    )
    (net (code "68") (name "unconnected-(U9-SIN_USO-Pad4)") (class "Default")
      (node (ref "U9") (pin "4") (pinfunction "SIN_USO_4") (pintype "passive"))
    )
    (net (code "69") (name "unconnected-(U9-VIDEO_OUT-Pad2)") (class "Default")
      (node (ref "U9") (pin "2") (pinfunction "VIDEO_OUT_2") (pintype "passive"))
    )
    (net (code "70") (name "unconnected-(U10-SIN_USO-Pad4)") (class "Default")
      (node (ref "U10") (pin "4") (pinfunction "SIN_USO_4") (pintype "passive"))
    )
    (net (code "71") (name "unconnected-(U10-VIDEO_OUT-Pad2)") (class "Default")
      (node (ref "U10") (pin "2") (pinfunction "VIDEO_OUT_2") (pintype "passive"))
    )
    (net (code "72") (name "unconnected-(U11-SIN_USO-Pad4)") (class "Default")
      (node (ref "U11") (pin "4") (pinfunction "SIN_USO_4") (pintype "passive"))
    )
    (net (code "73") (name "unconnected-(U11-VIDEO_OUT-Pad2)") (class "Default")
      (node (ref "U11") (pin "2") (pinfunction "VIDEO_OUT_2") (pintype "passive"))
    )
    (net (code "74") (name "unconnected-(U12-SIN_USO-Pad4)") (class "Default")
      (node (ref "U12") (pin "4") (pinfunction "SIN_USO_4") (pintype "passive"))
    )
    (net (code "75") (name "unconnected-(U12-VIDEO_OUT-Pad2)") (class "Default")
      (node (ref "U12") (pin "2") (pinfunction "VIDEO_OUT_2") (pintype "passive"))
    )
  )
)
